# Decoupling_Capacitors.net
KiCad netlist of a schematic drawn in Altium Designer
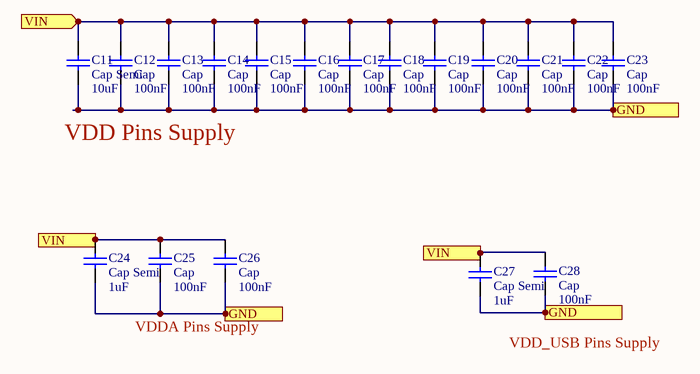
[diagram p0: Decoupling_Capacitors.SchDoc]

(export (version "E")
  (design (tool "Eeschema 10.0.6"))
  (components
    (comp (ref "C11")
      (value "Cap Semi")
      (footprint "CAP_TANT1206")
      (description "Tantalum Capacitors - Solid SMD 16V 10uF 1206 10% ESR=3Ohms")
      (fields (field (name "ALTIUM_VALUE") "10uF"))
      (libsource (lib "Miscellaneous Devices") (part "Cap Semi"))
    )
    (comp (ref "C12")
      (value "Cap")
      (footprint "0402")
      (description "Multilayer Ceramic Capacitors MLCC - SMD/SMT 16volts 0.1uF 20% X7R")
      (fields (field (name "ALTIUM_VALUE") "100nF"))
      (libsource (lib "Miscellaneous Devices") (part "Cap"))
    )
    (comp (ref "C13")
      (value "Cap")
      (footprint "0402")
      (description "Multilayer Ceramic Capacitors MLCC - SMD/SMT 16volts 0.1uF 20% X7R")
      (fields (field (name "ALTIUM_VALUE") "100nF"))
      (libsource (lib "Miscellaneous Devices") (part "Cap"))
    )
    (comp (ref "C14")
      (value "Cap")
      (footprint "0402")
      (description "Multilayer Ceramic Capacitors MLCC - SMD/SMT 16volts 0.1uF 20% X7R")
      (fields (field (name "ALTIUM_VALUE") "100nF"))
      (libsource (lib "Miscellaneous Devices") (part "Cap"))
    )
    (comp (ref "C15")
      (value "Cap")
      (footprint "0402")
      (description "Multilayer Ceramic Capacitors MLCC - SMD/SMT 16volts 0.1uF 20% X7R")
      (fields (field (name "ALTIUM_VALUE") "100nF"))
      (libsource (lib "Miscellaneous Devices") (part "Cap"))
    )
    (comp (ref "C16")
      (value "Cap")
      (footprint "0402")
      (description "Multilayer Ceramic Capacitors MLCC - SMD/SMT 16volts 0.1uF 20% X7R")
      (fields (field (name "ALTIUM_VALUE") "100nF"))
      (libsource (lib "Miscellaneous Devices") (part "Cap"))
    )
    (comp (ref "C17")
      (value "Cap")
      (footprint "0402")
      (description "Multilayer Ceramic Capacitors MLCC - SMD/SMT 16volts 0.1uF 20% X7R")
      (fields (field (name "ALTIUM_VALUE") "100nF"))
      (libsource (lib "Miscellaneous Devices") (part "Cap"))
    )
    (comp (ref "C18")
      (value "Cap")
      (footprint "0402")
      (description "Multilayer Ceramic Capacitors MLCC - SMD/SMT 16volts 0.1uF 20% X7R")
      (fields (field (name "ALTIUM_VALUE") "100nF"))
      (libsource (lib "Miscellaneous Devices") (part "Cap"))
    )
    (comp (ref "C19")
      (value "Cap")
      (footprint "0402")
      (description "Multilayer Ceramic Capacitors MLCC - SMD/SMT 16volts 0.1uF 20% X7R")
      (fields (field (name "ALTIUM_VALUE") "100nF"))
      (libsource (lib "Miscellaneous Devices") (part "Cap"))
    )
    (comp (ref "C20")
      (value "Cap")
      (footprint "0402")
      (description "Multilayer Ceramic Capacitors MLCC - SMD/SMT 16volts 0.1uF 20% X7R")
      (fields (field (name "ALTIUM_VALUE") "100nF"))
      (libsource (lib "Miscellaneous Devices") (part "Cap"))
    )
    (comp (ref "C21")
      (value "Cap")
      (footprint "0402")
      (description "Multilayer Ceramic Capacitors MLCC - SMD/SMT 16volts 0.1uF 20% X7R")
      (fields (field (name "ALTIUM_VALUE") "100nF"))
      (libsource (lib "Miscellaneous Devices") (part "Cap"))
    )
    (comp (ref "C22")
      (value "Cap")
      (footprint "0402")
      (description "Multilayer Ceramic Capacitors MLCC - SMD/SMT 16volts 0.1uF 20% X7R")
      (fields (field (name "ALTIUM_VALUE") "100nF"))
      (libsource (lib "Miscellaneous Devices") (part "Cap"))
    )
    (comp (ref "C23")
      (value "Cap")
      (footprint "0402")
      (description "Multilayer Ceramic Capacitors MLCC - SMD/SMT 16volts 0.1uF 20% X7R")
      (fields (field (name "ALTIUM_VALUE") "100nF"))
      (libsource (lib "Miscellaneous Devices") (part "Cap"))
    )
    (comp (ref "C24")
      (value "Cap Semi")
      (footprint "0402")
      (description "Multilayer Ceramic Capacitors MLCC - SMD/SMT CGB 0402 16V 1uF JB 20%")
      (fields (field (name "ALTIUM_VALUE") "1uF"))
      (libsource (lib "Miscellaneous Devices") (part "Cap Semi"))
    )
    (comp (ref "C25")
      (value "Cap")
      (footprint "0402")
      (description "Multilayer Ceramic Capacitors MLCC - SMD/SMT 16volts 0.1uF 20% X7R")
      (fields (field (name "ALTIUM_VALUE") "100nF"))
      (libsource (lib "Miscellaneous Devices") (part "Cap"))
    )
    (comp (ref "C26")
      (value "Cap")
      (footprint "0402")
      (description "Multilayer Ceramic Capacitors MLCC - SMD/SMT 16volts 0.1uF 20% X7R")
      (fields (field (name "ALTIUM_VALUE") "100nF"))
      (libsource (lib "Miscellaneous Devices") (part "Cap"))
    )
    (comp (ref "C27")
      (value "Cap Semi")
      (footprint "0402")
      (description "Multilayer Ceramic Capacitors MLCC - SMD/SMT CGB 0402 16V 1uF JB 20%")
      (fields (field (name "ALTIUM_VALUE") "1uF"))
      (libsource (lib "Miscellaneous Devices") (part "Cap Semi"))
    )
    (comp (ref "C28")
      (value "Cap")
      (footprint "0402")
      (description "Multilayer Ceramic Capacitors MLCC - SMD/SMT 16volts 0.1uF 20% X7R")
      (fields (field (name "ALTIUM_VALUE") "100nF"))
      (libsource (lib "Miscellaneous Devices") (part "Cap"))
    )
  )
  (nets
    (net (code "1") (name "/GND") (class "Default")
      (node (ref "C11") (pin "1") (pinfunction "1_1") (pintype "passive"))
      (node (ref "C12") (pin "1") (pinfunction "1_1") (pintype "passive"))
      (node (ref "C13") (pin "1") (pinfunction "1_1") (pintype "passive"))
      (node (ref "C14") (pin "1") (pinfunction "1_1") (pintype "passive"))
      (node (ref "C15") (pin "1") (pinfunction "1_1") (pintype "passive"))
      (node (ref "C16") (pin "1") (pinfunction "1_1") (pintype "passive"))
      (node (ref "C17") (pin "1") (pinfunction "1_1") (pintype "passive"))
      (node (ref "C18") (pin "1") (pinfunction "1_1") (pintype "passive"))
      (node (ref "C19") (pin "1") (pinfunction "1_1") (pintype "passive"))
      (node (ref "C20") (pin "1") (pinfunction "1_1") (pintype "passive"))
      (node (ref "C21") (pin "1") (pinfunction "1_1") (pintype "passive"))
      (node (ref "C22") (pin "1") (pinfunction "1_1") (pintype "passive"))
      (node (ref "C23") (pin "1") (pinfunction "1_1") (pintype "passive"))
      (node (ref "C25") (pin "1") (pinfunction "1_1") (pintype "passive"))
      (node (ref "C26") (pin "1") (pinfunction "1_1") (pintype "passive"))
      (node (ref "C27") (pin "1") (pinfunction "1_1") (pintype "passive"))
      (node (ref "C28") (pin "1") (pinfunction "1_1") (pintype "passive"))
    )
    (net (code "2") (name "/VIN") (class "Default")
      (node (ref "C11") (pin "2") (pinfunction "2_2") (pintype "passive"))
      (node (ref "C12") (pin "2") (pinfunction "2_2") (pintype "passive"))
      (node (ref "C13") (pin "2") (pinfunction "2_2") (pintype "passive"))
      (node (ref "C14") (pin "2") (pinfunction "2_2") (pintype "passive"))
      (node (ref "C15") (pin "2") (pinfunction "2_2") (pintype "passive"))
      (node (ref "C16") (pin "2") (pinfunction "2_2") (pintype "passive"))
      (node (ref "C17") (pin "2") (pinfunction "2_2") (pintype "passive"))
      (node (ref "C18") (pin "2") (pinfunction "2_2") (pintype "passive"))
      (node (ref "C19") (pin "2") (pinfunction "2_2") (pintype "passive"))
      (node (ref "C20") (pin "2") (pinfunction "2_2") (pintype "passive"))
      (node (ref "C21") (pin "2") (pinfunction "2_2") (pintype "passive"))
      (node (ref "C22") (pin "2") (pinfunction "2_2") (pintype "passive"))
      (node (ref "C23") (pin "2") (pinfunction "2_2") (pintype "passive"))
      (node (ref "C24") (pin "2") (pinfunction "2_2") (pintype "passive"))
      (node (ref "C25") (pin "2") (pinfunction "2_2") (pintype "passive"))
      (node (ref "C26") (pin "2") (pinfunction "2_2") (pintype "passive"))
      (node (ref "C27") (pin "2") (pinfunction "2_2") (pintype "passive"))
      (node (ref "C28") (pin "2") (pinfunction "2_2") (pintype "passive"))
    )
    (net (code "3") (name "unconnected-(C24-Pad1)") (class "Default")
      (node (ref "C24") (pin "1") (pinfunction "1_1") (pintype "passive"))
    )
  )
)
